# Flexprint_Serverport.net
KiCad netlist of a schematic drawn in Altium Designer
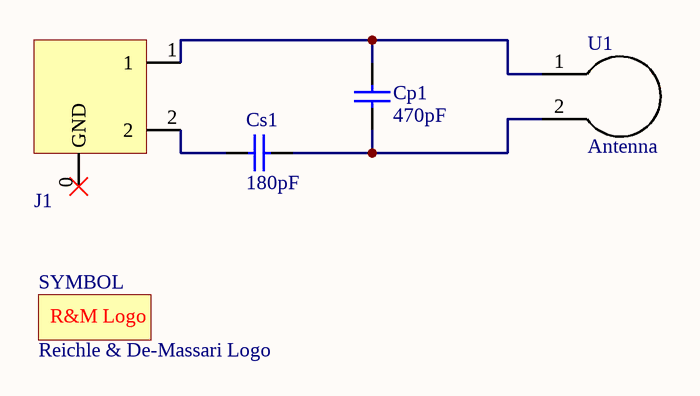
[diagram p0: Flexprint_Serverport.SchDoc]

(export (version "E")
  (design (tool "Eeschema 10.0.6"))
  (components
    (comp (ref "Cp1")
      (value "470pF")
      (footprint "C0402")
      (description "470pF ±1% 50V Ceramic Capacitor C0G, NP0 0402 (1005 Metric)")
      (fields (field (name "MANUFACTURER") "Murata") (field (name "TOLERANCE") "±1%"))
      (libsource (lib "Flexprint_Serverport") (part "Cap_470pF_0402"))
    )
    (comp (ref "Cs1")
      (value "180pF")
      (footprint "C0402")
      (description "180pF ±1% 50V Ceramic Capacitor C0G, NP0 0402 (1005 Metric)")
      (fields (field (name "MANUFACTURER") "Murata") (field (name "TOLERANCE") "±1%"))
      (libsource (lib "Flexprint_Serverport") (part "Cap_180pF_0402"))
    )
    (comp (ref "J1")
      (value "Molex 0781710002")
      (footprint "CONN_2x1")
      (description "Molex, connector Header SMD, 2 position 0.047\" (1.20mm)")
      (fields (field (name "MANUFACTURER") "Molex"))
      (libsource (lib "Flexprint_Serverport") (part "Conn_2x1"))
    )
    (comp (ref "SYMBOL")
      (value "Reichle & De-Massari Logo")
      (footprint "SYMBOL_R&M")
      (libsource (lib "Flexprint_Serverport") (part "SYMBOL_R&M"))
    )
    (comp (ref "U1")
      (value "Antenna")
      (footprint "Ant")
      (libsource (lib "Flexprint_Serverport") (part "Antenna"))
    )
  )
  (nets
    (net (code "1") (name "Net-(Cp1-Pad1)") (class "Default")
      (node (ref "Cp1") (pin "1") (pinfunction "1_1") (pintype "passive"))
      (node (ref "Cs1") (pin "1") (pinfunction "1_1") (pintype "passive"))
      (node (ref "U1") (pin "2") (pinfunction "2_2") (pintype "passive"))
    )
    (net (code "2") (name "Net-(Cp1-Pad2)") (class "Default")
      (node (ref "Cp1") (pin "2") (pinfunction "2_2") (pintype "passive"))
      (node (ref "J1") (pin "1") (pinfunction "1_1") (pintype "passive"))
      (node (ref "U1") (pin "1") (pinfunction "1_1") (pintype "passive"))
    )
    (net (code "3") (name "Net-(Cs1-Pad2)") (class "Default")
      (node (ref "Cs1") (pin "2") (pinfunction "2_2") (pintype "passive"))
      (node (ref "J1") (pin "2") (pinfunction "2_2") (pintype "passive"))
    )
    (net (code "4") (name "unconnected-(J1-GND-Pad0)") (class "Default")
      (node (ref "J1") (pin "0") (pinfunction "GND_0") (pintype "power_in+no_connect"))
    )
  )
)
